# Power.net
KiCad netlist of a schematic drawn in Altium Designer
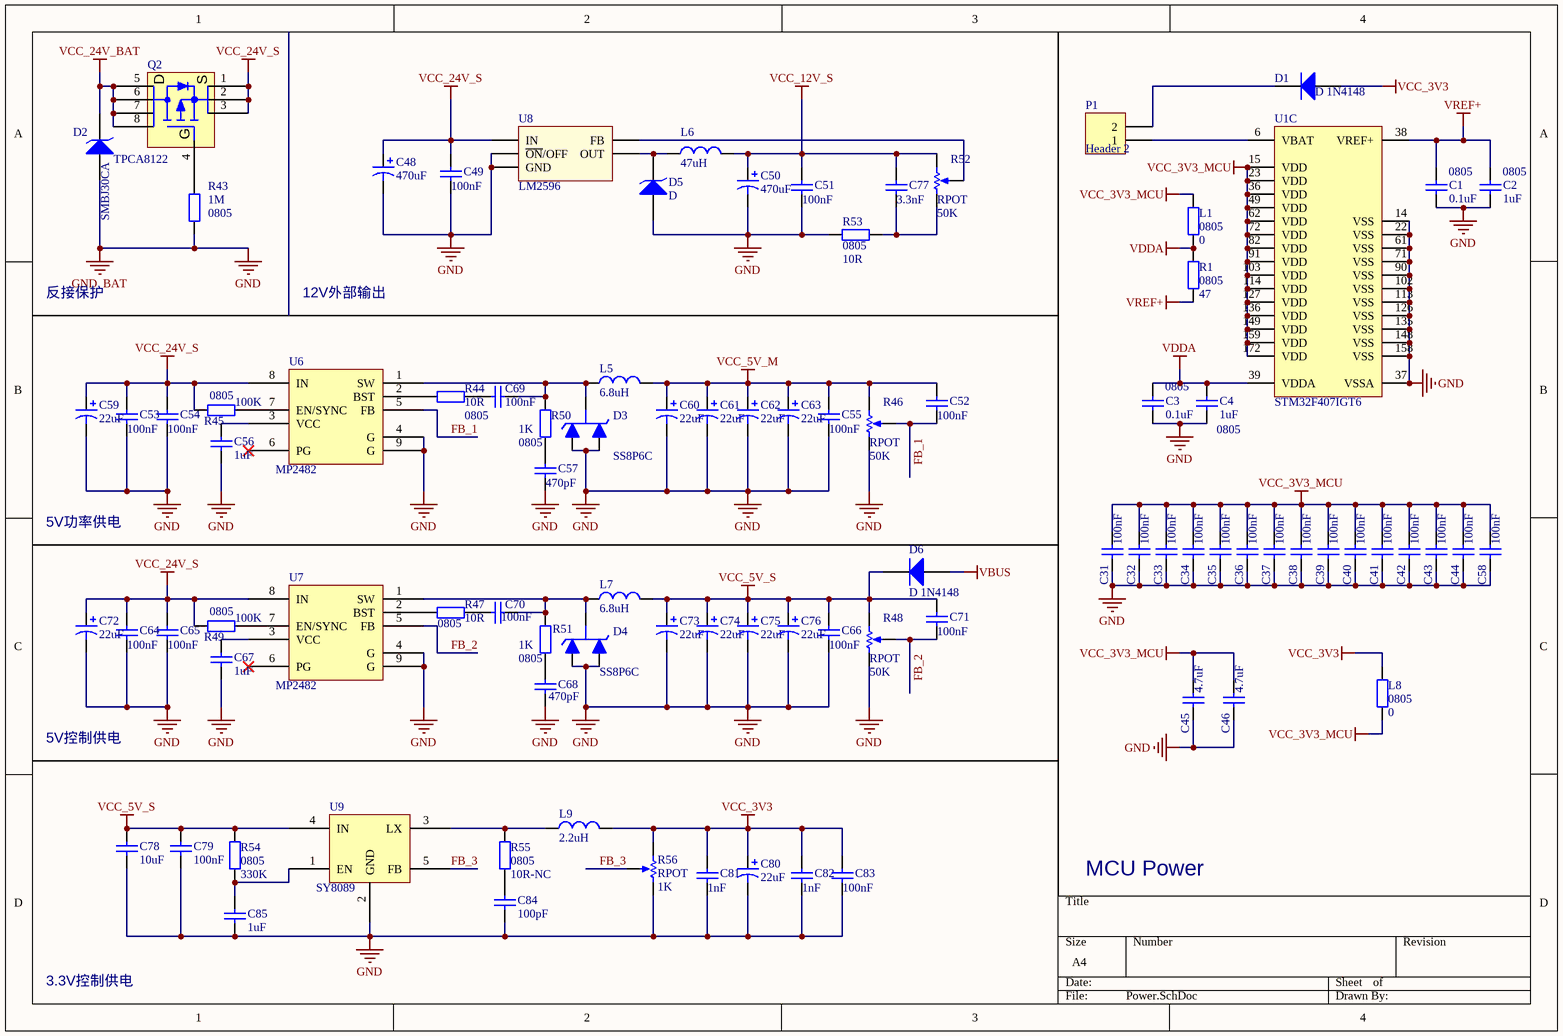
[diagram p0: Power.SchDoc]

(export (version "E")
  (design (tool "Eeschema 10.0.6"))
  (components
    (comp (ref "C1")
      (value "0805")
      (footprint "C 0603_L")
      (fields (field (name "ALTIUM_VALUE") "0.1uF"))
      (libsource (lib "QT") (part "CAP"))
    )
    (comp (ref "C2")
      (value "0805")
      (footprint "C 0603_L")
      (fields (field (name "ALTIUM_VALUE") "1uF"))
      (libsource (lib "QT") (part "CAP"))
    )
    (comp (ref "C3")
      (value "0805")
      (footprint "C 0603_L")
      (fields (field (name "ALTIUM_VALUE") "0.1uF"))
      (libsource (lib "QT") (part "CAP"))
    )
    (comp (ref "C4")
      (value "0805")
      (footprint "C 0603_L")
      (fields (field (name "ALTIUM_VALUE") "1uF"))
      (libsource (lib "QT") (part "CAP"))
    )
    (comp (ref "C31")
      (value "100nF")
      (footprint "C 0603_L")
      (fields (field (name "Comment") "0805"))
      (libsource (lib "QT") (part "CAP"))
    )
    (comp (ref "C32")
      (value "100nF")
      (footprint "C 0603_L")
      (fields (field (name "Comment") "0805"))
      (libsource (lib "QT") (part "CAP"))
    )
    (comp (ref "C33")
      (value "100nF")
      (footprint "C 0603_L")
      (fields (field (name "Comment") "0805"))
      (libsource (lib "QT") (part "CAP"))
    )
    (comp (ref "C34")
      (value "100nF")
      (footprint "C 0603_L")
      (fields (field (name "Comment") "0805"))
      (libsource (lib "QT") (part "CAP"))
    )
    (comp (ref "C35")
      (value "100nF")
      (footprint "C 0603_L")
      (fields (field (name "Comment") "0805"))
      (libsource (lib "QT") (part "CAP"))
    )
    (comp (ref "C36")
      (value "100nF")
      (footprint "C 0603_L")
      (fields (field (name "Comment") "0805"))
      (libsource (lib "QT") (part "CAP"))
    )
    (comp (ref "C37")
      (value "100nF")
      (footprint "C 0603_L")
      (fields (field (name "Comment") "0805"))
      (libsource (lib "QT") (part "CAP"))
    )
    (comp (ref "C38")
      (value "100nF")
      (footprint "C 0603_L")
      (fields (field (name "Comment") "0805"))
      (libsource (lib "QT") (part "CAP"))
    )
    (comp (ref "C39")
      (value "100nF")
      (footprint "C 0603_L")
      (fields (field (name "Comment") "0805"))
      (libsource (lib "QT") (part "CAP"))
    )
    (comp (ref "C40")
      (value "100nF")
      (footprint "C 0603_L")
      (fields (field (name "Comment") "0805"))
      (libsource (lib "QT") (part "CAP"))
    )
    (comp (ref "C41")
      (value "100nF")
      (footprint "C 0603_L")
      (fields (field (name "Comment") "0805"))
      (libsource (lib "QT") (part "CAP"))
    )
    (comp (ref "C42")
      (value "100nF")
      (footprint "C 0603_L")
      (fields (field (name "Comment") "0805"))
      (libsource (lib "QT") (part "CAP"))
    )
    (comp (ref "C43")
      (value "100nF")
      (footprint "C 0603_L")
      (fields (field (name "Comment") "0805"))
      (libsource (lib "QT") (part "CAP"))
    )
    (comp (ref "C44")
      (value "100nF")
      (footprint "C 0603_L")
      (fields (field (name "Comment") "0805"))
      (libsource (lib "QT") (part "CAP"))
    )
    (comp (ref "C45")
      (value "4.7uF")
      (footprint "C 0805_M")
      (fields (field (name "Comment") "0805"))
      (libsource (lib "QT") (part "CAP"))
    )
    (comp (ref "C46")
      (value "4.7uF")
      (footprint "C 0805_M")
      (fields (field (name "Comment") "0805"))
      (libsource (lib "QT") (part "CAP"))
    )
    (comp (ref "C48")
      (value "470uF")
      (footprint "CM E(8*10.2)")
      (fields (field (name "Comment") "CAP-ELEC"))
      (libsource (lib "QT") (part "CAP-ELEC"))
    )
    (comp (ref "C49")
      (value "100nF")
      (footprint "C 0805_L")
      (fields (field (name "Comment") "CAP"))
      (libsource (lib "QT") (part "CAP"))
    )
    (comp (ref "C50")
      (value "470uF")
      (footprint "CM E(8*10.2)")
      (fields (field (name "Comment") "CAP-ELEC"))
      (libsource (lib "QT") (part "CAP-ELEC"))
    )
    (comp (ref "C51")
      (value "100nF")
      (footprint "C 0805_L")
      (fields (field (name "Comment") "CAP"))
      (libsource (lib "QT") (part "CAP"))
    )
    (comp (ref "C52")
      (value "100nF")
      (footprint "C 0805_L")
      (fields (field (name "Comment") "CAP"))
      (libsource (lib "QT") (part "CAP"))
    )
    (comp (ref "C53")
      (value "100nF")
      (footprint "C 0805_L")
      (fields (field (name "Comment") "CAP"))
      (libsource (lib "QT") (part "CAP"))
    )
    (comp (ref "C54")
      (value "100nF")
      (footprint "C 0805_L")
      (fields (field (name "Comment") "CAP"))
      (libsource (lib "QT") (part "CAP"))
    )
    (comp (ref "C55")
      (value "100nF")
      (footprint "C 0805_L")
      (fields (field (name "Comment") "CAP"))
      (libsource (lib "QT") (part "CAP"))
    )
    (comp (ref "C56")
      (value "1uF")
      (footprint "C 0805_L")
      (fields (field (name "Comment") "CAP"))
      (libsource (lib "QT") (part "CAP"))
    )
    (comp (ref "C57")
      (value "470pF")
      (footprint "C 0805_L")
      (fields (field (name "Comment") "CAP"))
      (libsource (lib "QT") (part "CAP"))
    )
    (comp (ref "C58")
      (value "100nF")
      (footprint "C 0603_L")
      (fields (field (name "Comment") "0805"))
      (libsource (lib "QT") (part "CAP"))
    )
    (comp (ref "C59")
      (value "22uF")
      (footprint "CD C(6032)")
      (fields (field (name "Comment") "CAP-ELEC"))
      (libsource (lib "QT") (part "CAP-ELEC"))
    )
    (comp (ref "C60")
      (value "22uF")
      (footprint "CD C(6032)")
      (fields (field (name "Comment") "CAP-ELEC"))
      (libsource (lib "QT") (part "CAP-ELEC"))
    )
    (comp (ref "C61")
      (value "22uF")
      (footprint "CD C(6032)")
      (fields (field (name "Comment") "CAP-ELEC"))
      (libsource (lib "QT") (part "CAP-ELEC"))
    )
    (comp (ref "C62")
      (value "22uF")
      (footprint "CD C(6032)")
      (fields (field (name "Comment") "CAP-ELEC"))
      (libsource (lib "QT") (part "CAP-ELEC"))
    )
    (comp (ref "C63")
      (value "22uF")
      (footprint "CD C(6032)")
      (fields (field (name "Comment") "CAP-ELEC"))
      (libsource (lib "QT") (part "CAP-ELEC"))
    )
    (comp (ref "C64")
      (value "100nF")
      (footprint "C 0805_L")
      (fields (field (name "Comment") "CAP"))
      (libsource (lib "QT") (part "CAP"))
    )
    (comp (ref "C65")
      (value "100nF")
      (footprint "C 0805_L")
      (fields (field (name "Comment") "CAP"))
      (libsource (lib "QT") (part "CAP"))
    )
    (comp (ref "C66")
      (value "100nF")
      (footprint "C 0805_L")
      (fields (field (name "Comment") "CAP"))
      (libsource (lib "QT") (part "CAP"))
    )
    (comp (ref "C67")
      (value "1uF")
      (footprint "C 0805_L")
      (fields (field (name "Comment") "CAP"))
      (libsource (lib "QT") (part "CAP"))
    )
    (comp (ref "C68")
      (value "470pF")
      (footprint "C 0805_L")
      (fields (field (name "Comment") "CAP"))
      (libsource (lib "QT") (part "CAP"))
    )
    (comp (ref "C69")
      (value "100nF")
      (footprint "C 0805_L")
      (fields (field (name "Comment") "CAP"))
      (libsource (lib "QT") (part "CAP"))
    )
    (comp (ref "C70")
      (value "100nF")
      (footprint "C 0805_L")
      (fields (field (name "Comment") "CAP"))
      (libsource (lib "QT") (part "CAP"))
    )
    (comp (ref "C71")
      (value "100nF")
      (footprint "C 0805_L")
      (fields (field (name "Comment") "CAP"))
      (libsource (lib "QT") (part "CAP"))
    )
    (comp (ref "C72")
      (value "22uF")
      (footprint "CD C(6032)")
      (fields (field (name "Comment") "CAP-ELEC"))
      (libsource (lib "QT") (part "CAP-ELEC"))
    )
    (comp (ref "C73")
      (value "22uF")
      (footprint "CD C(6032)")
      (fields (field (name "Comment") "CAP-ELEC"))
      (libsource (lib "QT") (part "CAP-ELEC"))
    )
    (comp (ref "C74")
      (value "22uF")
      (footprint "CD C(6032)")
      (fields (field (name "Comment") "CAP-ELEC"))
      (libsource (lib "QT") (part "CAP-ELEC"))
    )
    (comp (ref "C75")
      (value "22uF")
      (footprint "CD C(6032)")
      (fields (field (name "Comment") "CAP-ELEC"))
      (libsource (lib "QT") (part "CAP-ELEC"))
    )
    (comp (ref "C76")
      (value "22uF")
      (footprint "CD C(6032)")
      (fields (field (name "Comment") "CAP-ELEC"))
      (libsource (lib "QT") (part "CAP-ELEC"))
    )
    (comp (ref "C77")
      (value "3.3nF")
      (footprint "C 0805_L")
      (fields (field (name "Comment") "CAP"))
      (libsource (lib "QT") (part "CAP"))
    )
    (comp (ref "C78")
      (value "10uF")
      (footprint "C 0805_L")
      (fields (field (name "Comment") "CAP"))
      (libsource (lib "QT") (part "CAP"))
    )
    (comp (ref "C79")
      (value "100nF")
      (footprint "C 0805_L")
      (fields (field (name "Comment") "CAP"))
      (libsource (lib "QT") (part "CAP"))
    )
    (comp (ref "C80")
      (value "22uF")
      (footprint "CD C(6032)")
      (fields (field (name "Comment") "CAP-ELEC"))
      (libsource (lib "QT") (part "CAP-ELEC"))
    )
    (comp (ref "C81")
      (value "1nF")
      (footprint "C 0805_L")
      (fields (field (name "Comment") "CAP"))
      (libsource (lib "QT") (part "CAP"))
    )
    (comp (ref "C82")
      (value "1nF")
      (footprint "C 0805_L")
      (fields (field (name "Comment") "CAP"))
      (libsource (lib "QT") (part "CAP"))
    )
    (comp (ref "C83")
      (value "100nF")
      (footprint "C 0805_L")
      (fields (field (name "Comment") "CAP"))
      (libsource (lib "QT") (part "CAP"))
    )
    (comp (ref "C84")
      (value "100pF")
      (footprint "C 0805_L")
      (fields (field (name "Comment") "CAP"))
      (libsource (lib "QT") (part "CAP"))
    )
    (comp (ref "C85")
      (value "1uF")
      (footprint "C 0805_L")
      (fields (field (name "Comment") "CAP"))
      (libsource (lib "QT") (part "CAP"))
    )
    (comp (ref "D1")
      (value "D 1N4148")
      (footprint "SOD-523")
      (description "High Conductance Fast Diode")
      (fields (field (name "PUBLISHER") "Altium Limited"))
      (libsource (lib "QT") (part "D 1N4148"))
    )
    (comp (ref "D2")
      (value "SMBJ30CA")
      (footprint "SMB")
      (description "High Conductance Fast Diode")
      (fields (field (name "PUBLISHER") "Altium Limited"))
      (libsource (lib "QT") (part "D"))
    )
    (comp (ref "D3") (value "SS8P6C") (footprint "TO-277") (libsource (lib "常用元件库") (part "SS8P6C")))
    (comp (ref "D4") (value "SS8P6C") (footprint "TO-277") (libsource (lib "常用元件库") (part "SS8P6C")))
    (comp (ref "D5")
      (value "D")
      (footprint "SOD-123")
      (description "High Conductance Fast Diode")
      (fields (field (name "PUBLISHER") "Altium Limited"))
      (libsource (lib "QT") (part "D"))
    )
    (comp (ref "D6")
      (value "D 1N4148")
      (footprint "SOD-123")
      (description "High Conductance Fast Diode")
      (fields (field (name "PUBLISHER") "Altium Limited"))
      (libsource (lib "QT") (part "D 1N4148"))
    )
    (comp (ref "L1")
      (value "0805")
      (footprint "R 0402_L")
      (description "Resistor")
      (fields (field (name "ALTIUM_VALUE") "0") (field (name "PUBLISHER") "Altium Limited"))
      (libsource (lib "QT") (part "RES2"))
    )
    (comp (ref "L5")
      (value "6.8uH")
      (footprint "L-SMD-10")
      (description "电感")
      (fields (field (name "Comment") "Inductor") (field (name "PUBLISHER") "Altium Limited"))
      (libsource (lib "Fszhang") (part "Inductor"))
    )
    (comp (ref "L6")
      (value "47uH")
      (footprint "L-SMD-12")
      (description "电感")
      (fields (field (name "Comment") "Inductor") (field (name "PUBLISHER") "Altium Limited"))
      (libsource (lib "Fszhang") (part "Inductor"))
    )
    (comp (ref "L7")
      (value "6.8uH")
      (footprint "L-SMD-10")
      (description "电感")
      (fields (field (name "Comment") "Inductor") (field (name "PUBLISHER") "Altium Limited"))
      (libsource (lib "Fszhang") (part "Inductor"))
    )
    (comp (ref "L8")
      (value "0805")
      (footprint "R 0402_L")
      (description "Resistor")
      (fields (field (name "ALTIUM_VALUE") "0") (field (name "PUBLISHER") "Altium Limited"))
      (libsource (lib "QT") (part "RES2"))
    )
    (comp (ref "L9")
      (value "2.2uH")
      (footprint "CD52")
      (description "电感")
      (fields (field (name "Comment") "Inductor") (field (name "PUBLISHER") "Altium Limited"))
      (libsource (lib "Fszhang") (part "Inductor"))
    )
    (comp (ref "P1")
      (value "Header 2")
      (footprint "HDR2.54-LI-2P")
      (description "Header, 2-Pin")
      (fields (field (name "PUBLISHER") "Altium Limited"))
      (libsource (lib "QT") (part "Header 2"))
    )
    (comp (ref "Q2") (value "TPCA8122") (footprint "PSOP8") (libsource (lib "常用元件库") (part "TPCA8122")))
    (comp (ref "R1")
      (value "0805")
      (footprint "R 0402_L")
      (description "Resistor")
      (fields (field (name "ALTIUM_VALUE") "47") (field (name "PUBLISHER") "Altium Limited"))
      (libsource (lib "QT") (part "RES2"))
    )
    (comp (ref "R43")
      (value "0805")
      (footprint "R 0805_L")
      (description "Resistor")
      (fields (field (name "ALTIUM_VALUE") "1M") (field (name "PUBLISHER") "Altium Limited"))
      (libsource (lib "QT") (part "RES2"))
    )
    (comp (ref "R44")
      (value "0805")
      (footprint "R 0805_L")
      (description "Resistor")
      (fields (field (name "ALTIUM_VALUE") "10R") (field (name "PUBLISHER") "Altium Limited"))
      (libsource (lib "") (part "RES2_2"))
    )
    (comp (ref "R45")
      (value "0805")
      (footprint "R 0805_L")
      (description "Resistor")
      (fields (field (name "ALTIUM_VALUE") "100K") (field (name "PUBLISHER") "Altium Limited"))
      (libsource (lib "") (part "RES2_2"))
    )
    (comp (ref "R46")
      (value "RPOT")
      (footprint "3296W")
      (description "Potentiometer")
      (fields (field (name "ALTIUM_VALUE") "50K") (field (name "PUBLISHER") "Altium Limited"))
      (libsource (lib "QT") (part "RPOT"))
    )
    (comp (ref "R47")
      (value "0805")
      (footprint "R 0805_L")
      (description "Resistor")
      (fields (field (name "ALTIUM_VALUE") "10R") (field (name "PUBLISHER") "Altium Limited"))
      (libsource (lib "") (part "RES2_2"))
    )
    (comp (ref "R48")
      (value "RPOT")
      (footprint "3296W")
      (description "Potentiometer")
      (fields (field (name "ALTIUM_VALUE") "50K") (field (name "PUBLISHER") "Altium Limited"))
      (libsource (lib "QT") (part "RPOT"))
    )
    (comp (ref "R49")
      (value "0805")
      (footprint "R 0805_L")
      (description "Resistor")
      (fields (field (name "ALTIUM_VALUE") "100K") (field (name "PUBLISHER") "Altium Limited"))
      (libsource (lib "") (part "RES2_2"))
    )
    (comp (ref "R50")
      (value "0805")
      (footprint "R 0805_L")
      (description "Resistor")
      (fields (field (name "ALTIUM_VALUE") "1K") (field (name "PUBLISHER") "Altium Limited"))
      (libsource (lib "QT") (part "RES2"))
    )
    (comp (ref "R51")
      (value "0805")
      (footprint "R 0805_L")
      (description "Resistor")
      (fields (field (name "ALTIUM_VALUE") "1K") (field (name "PUBLISHER") "Altium Limited"))
      (libsource (lib "QT") (part "RES2"))
    )
    (comp (ref "R52")
      (value "RPOT")
      (footprint "3296W")
      (description "Potentiometer")
      (fields (field (name "ALTIUM_VALUE") "50K") (field (name "PUBLISHER") "Altium Limited"))
      (libsource (lib "QT") (part "RPOT"))
    )
    (comp (ref "R53")
      (value "0805")
      (footprint "R 0805_L")
      (description "Resistor")
      (fields (field (name "ALTIUM_VALUE") "10R") (field (name "PUBLISHER") "Altium Limited"))
      (libsource (lib "") (part "RES2_1"))
    )
    (comp (ref "R54")
      (value "0805")
      (footprint "R 0805_L")
      (description "Resistor")
      (fields (field (name "ALTIUM_VALUE") "330K") (field (name "PUBLISHER") "Altium Limited"))
      (libsource (lib "QT") (part "RES2"))
    )
    (comp (ref "R55")
      (value "0805")
      (footprint "R 0805_L")
      (description "Resistor")
      (fields (field (name "ALTIUM_VALUE") "10R-NC") (field (name "PUBLISHER") "Altium Limited"))
      (libsource (lib "QT") (part "RES2"))
    )
    (comp (ref "R56")
      (value "RPOT")
      (footprint "3296W")
      (description "Potentiometer")
      (fields (field (name "ALTIUM_VALUE") "1K") (field (name "PUBLISHER") "Altium Limited"))
      (libsource (lib "QT") (part "RPOT"))
    )
    (comp (ref "U1")
      (value "STM32F407IGT6")
      (footprint "STM-LQFP176_N")
      (fields (field (name "MANUFACTURER") "STMicroelectronics"))
      (libsource (lib "STMicroelectronics STM32 F4") (part "STM32F407IGT6"))
    )
    (comp (ref "U6") (value "MP2482") (footprint "SOIC9N") (libsource (lib "常用元件库") (part "MP2482")))
    (comp (ref "U7") (value "MP2482") (footprint "SOIC9N") (libsource (lib "常用元件库") (part "MP2482")))
    (comp (ref "U8") (value "LM2596") (footprint "TO263-5A") (libsource (lib "QT") (part "LM2576S")))
    (comp (ref "U9") (value "SY8089") (footprint "SOT-23-5L") (libsource (lib "常用元件库") (part "SY8089")))
  )
  (nets
    (net (code "1") (name "/FB_1") (class "Default")
      (node (ref "C52") (pin "2") (pinfunction "2_2") (pintype "passive"))
      (node (ref "R46") (pin "2") (pintype "passive"))
      (node (ref "U6") (pin "5") (pinfunction "FB_5") (pintype "passive"))
    )
    (net (code "2") (name "/FB_2") (class "Default")
      (node (ref "C71") (pin "2") (pinfunction "2_2") (pintype "passive"))
      (node (ref "R48") (pin "2") (pintype "passive"))
      (node (ref "U7") (pin "5") (pinfunction "FB_5") (pintype "passive"))
    )
    (net (code "3") (name "/FB_3") (class "Default")
      (node (ref "R56") (pin "2") (pintype "passive"))
      (node (ref "U9") (pin "5") (pinfunction "FB_5") (pintype "passive"))
    )
    (net (code "4") (name "GND") (class "Default")
      (node (ref "C1") (pin "1") (pinfunction "1_1") (pintype "passive"))
      (node (ref "C2") (pin "1") (pinfunction "1_1") (pintype "passive"))
      (node (ref "C3") (pin "1") (pinfunction "1_1") (pintype "passive"))
      (node (ref "C31") (pin "1") (pinfunction "1_1") (pintype "passive"))
      (node (ref "C32") (pin "1") (pinfunction "1_1") (pintype "passive"))
      (node (ref "C33") (pin "1") (pinfunction "1_1") (pintype "passive"))
      (node (ref "C34") (pin "1") (pinfunction "1_1") (pintype "passive"))
      (node (ref "C35") (pin "1") (pinfunction "1_1") (pintype "passive"))
      (node (ref "C36") (pin "1") (pinfunction "1_1") (pintype "passive"))
      (node (ref "C37") (pin "1") (pinfunction "1_1") (pintype "passive"))
      (node (ref "C38") (pin "1") (pinfunction "1_1") (pintype "passive"))
      (node (ref "C39") (pin "1") (pinfunction "1_1") (pintype "passive"))
      (node (ref "C4") (pin "1") (pinfunction "1_1") (pintype "passive"))
      (node (ref "C40") (pin "1") (pinfunction "1_1") (pintype "passive"))
      (node (ref "C41") (pin "1") (pinfunction "1_1") (pintype "passive"))
      (node (ref "C42") (pin "1") (pinfunction "1_1") (pintype "passive"))
      (node (ref "C43") (pin "1") (pinfunction "1_1") (pintype "passive"))
      (node (ref "C44") (pin "1") (pinfunction "1_1") (pintype "passive"))
      (node (ref "C45") (pin "1") (pinfunction "1_1") (pintype "passive"))
      (node (ref "C46") (pin "1") (pinfunction "1_1") (pintype "passive"))
      (node (ref "C48") (pin "2") (pinfunction "2_2") (pintype "passive"))
      (node (ref "C49") (pin "2") (pinfunction "2_2") (pintype "passive"))
      (node (ref "C50") (pin "2") (pinfunction "2_2") (pintype "passive"))
      (node (ref "C51") (pin "2") (pinfunction "2_2") (pintype "passive"))
      (node (ref "C53") (pin "2") (pinfunction "2_2") (pintype "passive"))
      (node (ref "C54") (pin "2") (pinfunction "2_2") (pintype "passive"))
      (node (ref "C55") (pin "2") (pinfunction "2_2") (pintype "passive"))
      (node (ref "C56") (pin "1") (pinfunction "1_1") (pintype "passive"))
      (node (ref "C57") (pin "1") (pinfunction "1_1") (pintype "passive"))
      (node (ref "C58") (pin "1") (pinfunction "1_1") (pintype "passive"))
      (node (ref "C59") (pin "2") (pinfunction "2_2") (pintype "passive"))
      (node (ref "C60") (pin "2") (pinfunction "2_2") (pintype "passive"))
      (node (ref "C61") (pin "2") (pinfunction "2_2") (pintype "passive"))
      (node (ref "C62") (pin "2") (pinfunction "2_2") (pintype "passive"))
      (node (ref "C63") (pin "2") (pinfunction "2_2") (pintype "passive"))
      (node (ref "C64") (pin "2") (pinfunction "2_2") (pintype "passive"))
      (node (ref "C65") (pin "2") (pinfunction "2_2") (pintype "passive"))
      (node (ref "C66") (pin "2") (pinfunction "2_2") (pintype "passive"))
      (node (ref "C67") (pin "1") (pinfunction "1_1") (pintype "passive"))
      (node (ref "C68") (pin "1") (pinfunction "1_1") (pintype "passive"))
      (node (ref "C72") (pin "2") (pinfunction "2_2") (pintype "passive"))
      (node (ref "C73") (pin "2") (pinfunction "2_2") (pintype "passive"))
      (node (ref "C74") (pin "2") (pinfunction "2_2") (pintype "passive"))
      (node (ref "C75") (pin "2") (pinfunction "2_2") (pintype "passive"))
      (node (ref "C76") (pin "2") (pinfunction "2_2") (pintype "passive"))
      (node (ref "C78") (pin "1") (pinfunction "1_1") (pintype "passive"))
      (node (ref "C79") (pin "1") (pinfunction "1_1") (pintype "passive"))
      (node (ref "C80") (pin "2") (pinfunction "2_2") (pintype "passive"))
      (node (ref "C81") (pin "2") (pinfunction "2_2") (pintype "passive"))
      (node (ref "C82") (pin "2") (pinfunction "2_2") (pintype "passive"))
      (node (ref "C83") (pin "2") (pinfunction "2_2") (pintype "passive"))
      (node (ref "C84") (pin "1") (pinfunction "1_1") (pintype "passive"))
      (node (ref "C85") (pin "1") (pinfunction "1_1") (pintype "passive"))
      (node (ref "D2") (pin "1") (pinfunction "A_1") (pintype "passive"))
      (node (ref "D3") (pin "1") (pintype "passive"))
      (node (ref "D3") (pin "2") (pintype "passive"))
      (node (ref "D4") (pin "1") (pintype "passive"))
      (node (ref "D4") (pin "2") (pintype "passive"))
      (node (ref "D5") (pin "1") (pinfunction "A_1") (pintype "passive"))
      (node (ref "R43") (pin "1") (pinfunction "1_1") (pintype "passive"))
      (node (ref "R46") (pin "1") (pintype "passive"))
      (node (ref "R48") (pin "1") (pintype "passive"))
      (node (ref "R53") (pin "2") (pinfunction "2_2") (pintype "passive"))
      (node (ref "R56") (pin "3") (pintype "passive"))
      (node (ref "U1") (pin "102") (pinfunction "VSS_102") (pintype "power_in"))
      (node (ref "U1") (pin "113") (pinfunction "VSS_113") (pintype "power_in"))
      (node (ref "U1") (pin "126") (pinfunction "VSS_126") (pintype "power_in"))
      (node (ref "U1") (pin "135") (pinfunction "VSS_135") (pintype "power_in"))
      (node (ref "U1") (pin "14") (pinfunction "VSS_14") (pintype "power_in"))
      (node (ref "U1") (pin "148") (pinfunction "VSS_148") (pintype "power_in"))
      (node (ref "U1") (pin "158") (pinfunction "VSS_158") (pintype "power_in"))
      (node (ref "U1") (pin "22") (pinfunction "VSS_22") (pintype "power_in"))
      (node (ref "U1") (pin "37") (pinfunction "VSSA_37") (pintype "power_in"))
      (node (ref "U1") (pin "61") (pinfunction "VSS_61") (pintype "power_in"))
      (node (ref "U1") (pin "71") (pinfunction "VSS_71") (pintype "power_in"))
      (node (ref "U1") (pin "90") (pinfunction "VSS_90") (pintype "power_in"))
      (node (ref "U6") (pin "4") (pinfunction "G_4") (pintype "passive"))
      (node (ref "U6") (pin "9") (pinfunction "G_9") (pintype "passive"))
      (node (ref "U7") (pin "4") (pinfunction "G_4") (pintype "passive"))
      (node (ref "U7") (pin "9") (pinfunction "G_9") (pintype "passive"))
      (node (ref "U8") (pin "3") (pinfunction "GND_3") (pintype "passive"))
      (node (ref "U8") (pin "5") (pinfunction "~{ON}/OFF_5") (pintype "passive"))
      (node (ref "U9") (pin "2") (pinfunction "GND_2") (pintype "passive"))
    )
    (net (code "5") (name "Net-(C57-Pad2)") (class "Default")
      (node (ref "C57") (pin "2") (pinfunction "2_2") (pintype "passive"))
      (node (ref "R50") (pin "1") (pinfunction "1_1") (pintype "passive"))
    )
    (net (code "6") (name "Net-(C68-Pad2)") (class "Default")
      (node (ref "C68") (pin "2") (pinfunction "2_2") (pintype "passive"))
      (node (ref "R51") (pin "1") (pinfunction "1_1") (pintype "passive"))
    )
    (net (code "7") (name "Net-(C69-Pad2)") (class "Default")
      (node (ref "C69") (pin "2") (pinfunction "2_2") (pintype "passive"))
      (node (ref "R44") (pin "2") (pinfunction "2_2") (pintype "passive"))
    )
    (net (code "8") (name "Net-(C70-Pad2)") (class "Default")
      (node (ref "C70") (pin "2") (pinfunction "2_2") (pintype "passive"))
      (node (ref "R47") (pin "2") (pinfunction "2_2") (pintype "passive"))
    )
    (net (code "9") (name "Net-(C77-Pad2)") (class "Default")
      (node (ref "C77") (pin "2") (pinfunction "2_2") (pintype "passive"))
      (node (ref "R52") (pin "1") (pintype "passive"))
      (node (ref "R53") (pin "1") (pinfunction "1_1") (pintype "passive"))
    )
    (net (code "10") (name "Net-(C84-Pad2)") (class "Default")
      (node (ref "C84") (pin "2") (pinfunction "2_2") (pintype "passive"))
      (node (ref "R55") (pin "1") (pinfunction "1_1") (pintype "passive"))
    )
    (net (code "11") (name "Net-(D1-K)") (class "Default")
      (node (ref "D1") (pin "2") (pinfunction "K_2") (pintype "passive"))
      (node (ref "P1") (pin "2") (pinfunction "2_2") (pintype "passive"))
    )
    (net (code "12") (name "Net-(D5-K)") (class "Default")
      (node (ref "D5") (pin "2") (pinfunction "K_2") (pintype "passive"))
      (node (ref "L6") (pin "1") (pinfunction "1_1") (pintype "passive"))
      (node (ref "U8") (pin "2") (pinfunction "OUT_2") (pintype "passive"))
    )
    (net (code "13") (name "Net-(Q2-G)") (class "Default")
      (node (ref "Q2") (pin "4") (pinfunction "G_4") (pintype "passive"))
      (node (ref "R43") (pin "2") (pinfunction "2_2") (pintype "passive"))
    )
    (net (code "14") (name "Net-(U1C-VBAT)") (class "Default")
      (node (ref "P1") (pin "1") (pinfunction "1_1") (pintype "passive"))
      (node (ref "U1") (pin "6") (pinfunction "VBAT_6") (pintype "power_in"))
    )
    (net (code "15") (name "Net-(U6-BST)") (class "Default")
      (node (ref "R44") (pin "1") (pinfunction "1_1") (pintype "passive"))
      (node (ref "U6") (pin "2") (pinfunction "BST_2") (pintype "passive"))
    )
    (net (code "16") (name "Net-(U6-EN{slash}SYNC)") (class "Default")
      (node (ref "R45") (pin "2") (pinfunction "2_2") (pintype "passive"))
      (node (ref "U6") (pin "7") (pinfunction "EN/SYNC_7") (pintype "passive"))
    )
    (net (code "17") (name "Net-(U6-SW)") (class "Default")
      (node (ref "C69") (pin "1") (pinfunction "1_1") (pintype "passive"))
      (node (ref "D3") (pin "3") (pintype "passive"))
      (node (ref "L5") (pin "1") (pinfunction "1_1") (pintype "passive"))
      (node (ref "R50") (pin "2") (pinfunction "2_2") (pintype "passive"))
      (node (ref "U6") (pin "1") (pinfunction "SW_1") (pintype "passive"))
    )
    (net (code "18") (name "Net-(U6-VCC)") (class "Default")
      (node (ref "C56") (pin "2") (pinfunction "2_2") (pintype "passive"))
      (node (ref "U6") (pin "3") (pinfunction "VCC_3") (pintype "passive"))
    )
    (net (code "19") (name "Net-(U7-BST)") (class "Default")
      (node (ref "R47") (pin "1") (pinfunction "1_1") (pintype "passive"))
      (node (ref "U7") (pin "2") (pinfunction "BST_2") (pintype "passive"))
    )
    (net (code "20") (name "Net-(U7-EN{slash}SYNC)") (class "Default")
      (node (ref "R49") (pin "2") (pinfunction "2_2") (pintype "passive"))
      (node (ref "U7") (pin "7") (pinfunction "EN/SYNC_7") (pintype "passive"))
    )
    (net (code "21") (name "Net-(U7-SW)") (class "Default")
      (node (ref "C70") (pin "1") (pinfunction "1_1") (pintype "passive"))
      (node (ref "D4") (pin "3") (pintype "passive"))
      (node (ref "L7") (pin "1") (pinfunction "1_1") (pintype "passive"))
      (node (ref "R51") (pin "2") (pinfunction "2_2") (pintype "passive"))
      (node (ref "U7") (pin "1") (pinfunction "SW_1") (pintype "passive"))
    )
    (net (code "22") (name "Net-(U7-VCC)") (class "Default")
      (node (ref "C67") (pin "2") (pinfunction "2_2") (pintype "passive"))
      (node (ref "U7") (pin "3") (pinfunction "VCC_3") (pintype "passive"))
    )
    (net (code "23") (name "Net-(U8-FB)") (class "Default")
      (node (ref "R52") (pin "2") (pintype "passive"))
      (node (ref "U8") (pin "4") (pinfunction "FB_4") (pintype "passive"))
    )
    (net (code "24") (name "Net-(U9-EN)") (class "Default")
      (node (ref "C85") (pin "2") (pinfunction "2_2") (pintype "passive"))
      (node (ref "R54") (pin "1") (pinfunction "1_1") (pintype "passive"))
      (node (ref "U9") (pin "1") (pinfunction "EN_1") (pintype "passive"))
    )
    (net (code "25") (name "Net-(U9-LX)") (class "Default")
      (node (ref "L9") (pin "1") (pinfunction "1_1") (pintype "passive"))
      (node (ref "R55") (pin "2") (pinfunction "2_2") (pintype "passive"))
      (node (ref "U9") (pin "3") (pinfunction "LX_3") (pintype "passive"))
    )
    (net (code "26") (name "VBUS") (class "Default")
      (node (ref "D6") (pin "1") (pinfunction "A_1") (pintype "passive"))
    )
    (net (code "27") (name "VCC_3V3") (class "Default")
      (node (ref "C80") (pin "1") (pinfunction "1_1") (pintype "passive"))
      (node (ref "C81") (pin "1") (pinfunction "1_1") (pintype "passive"))
      (node (ref "C82") (pin "1") (pinfunction "1_1") (pintype "passive"))
      (node (ref "C83") (pin "1") (pinfunction "1_1") (pintype "passive"))
      (node (ref "D1") (pin "1") (pinfunction "A_1") (pintype "passive"))
      (node (ref "L8") (pin "2") (pinfunction "2_2") (pintype "passive"))
      (node (ref "L9") (pin "2") (pinfunction "2_2") (pintype "passive"))
      (node (ref "R56") (pin "1") (pintype "passive"))
    )
    (net (code "28") (name "VCC_3V3_MCU") (class "Default")
      (node (ref "C31") (pin "2") (pinfunction "2_2") (pintype "passive"))
      (node (ref "C32") (pin "2") (pinfunction "2_2") (pintype "passive"))
      (node (ref "C33") (pin "2") (pinfunction "2_2") (pintype "passive"))
      (node (ref "C34") (pin "2") (pinfunction "2_2") (pintype "passive"))
      (node (ref "C35") (pin "2") (pinfunction "2_2") (pintype "passive"))
      (node (ref "C36") (pin "2") (pinfunction "2_2") (pintype "passive"))
      (node (ref "C37") (pin "2") (pinfunction "2_2") (pintype "passive"))
      (node (ref "C38") (pin "2") (pinfunction "2_2") (pintype "passive"))
      (node (ref "C39") (pin "2") (pinfunction "2_2") (pintype "passive"))
      (node (ref "C40") (pin "2") (pinfunction "2_2") (pintype "passive"))
      (node (ref "C41") (pin "2") (pinfunction "2_2") (pintype "passive"))
      (node (ref "C42") (pin "2") (pinfunction "2_2") (pintype "passive"))
      (node (ref "C43") (pin "2") (pinfunction "2_2") (pintype "passive"))
      (node (ref "C44") (pin "2") (pinfunction "2_2") (pintype "passive"))
      (node (ref "C45") (pin "2") (pinfunction "2_2") (pintype "passive"))
      (node (ref "C46") (pin "2") (pinfunction "2_2") (pintype "passive"))
      (node (ref "C58") (pin "2") (pinfunction "2_2") (pintype "passive"))
      (node (ref "L1") (pin "2") (pinfunction "2_2") (pintype "passive"))
      (node (ref "L8") (pin "1") (pinfunction "1_1") (pintype "passive"))
      (node (ref "U1") (pin "103") (pinfunction "VDD_103") (pintype "power_in"))
      (node (ref "U1") (pin "114") (pinfunction "VDD_114") (pintype "power_in"))
      (node (ref "U1") (pin "127") (pinfunction "VDD_127") (pintype "power_in"))
      (node (ref "U1") (pin "136") (pinfunction "VDD_136") (pintype "power_in"))
      (node (ref "U1") (pin "149") (pinfunction "VDD_149") (pintype "power_in"))
      (node (ref "U1") (pin "15") (pinfunction "VDD_15") (pintype "power_in"))
      (node (ref "U1") (pin "159") (pinfunction "VDD_159") (pintype "power_in"))
      (node (ref "U1") (pin "172") (pinfunction "VDD_172") (pintype "power_in"))
      (node (ref "U1") (pin "23") (pinfunction "VDD_23") (pintype "power_in"))
      (node (ref "U1") (pin "36") (pinfunction "VDD_36") (pintype "power_in"))
      (node (ref "U1") (pin "49") (pinfunction "VDD_49") (pintype "power_in"))
      (node (ref "U1") (pin "62") (pinfunction "VDD_62") (pintype "power_in"))
      (node (ref "U1") (pin "72") (pinfunction "VDD_72") (pintype "power_in"))
      (node (ref "U1") (pin "82") (pinfunction "VDD_82") (pintype "power_in"))
      (node (ref "U1") (pin "91") (pinfunction "VDD_91") (pintype "power_in"))
    )
    (net (code "29") (name "VCC_5V_M") (class "Default")
      (node (ref "C52") (pin "1") (pinfunction "1_1") (pintype "passive"))
      (node (ref "C55") (pin "1") (pinfunction "1_1") (pintype "passive"))
      (node (ref "C60") (pin "1") (pinfunction "1_1") (pintype "passive"))
      (node (ref "C61") (pin "1") (pinfunction "1_1") (pintype "passive"))
      (node (ref "C62") (pin "1") (pinfunction "1_1") (pintype "passive"))
      (node (ref "C63") (pin "1") (pinfunction "1_1") (pintype "passive"))
      (node (ref "L5") (pin "2") (pinfunction "2_2") (pintype "passive"))
      (node (ref "R46") (pin "3") (pintype "passive"))
    )
    (net (code "30") (name "VCC_5V_S") (class "Default")
      (node (ref "C66") (pin "1") (pinfunction "1_1") (pintype "passive"))
      (node (ref "C71") (pin "1") (pinfunction "1_1") (pintype "passive"))
      (node (ref "C73") (pin "1") (pinfunction "1_1") (pintype "passive"))
      (node (ref "C74") (pin "1") (pinfunction "1_1") (pintype "passive"))
      (node (ref "C75") (pin "1") (pinfunction "1_1") (pintype "passive"))
      (node (ref "C76") (pin "1") (pinfunction "1_1") (pintype "passive"))
      (node (ref "C78") (pin "2") (pinfunction "2_2") (pintype "passive"))
      (node (ref "C79") (pin "2") (pinfunction "2_2") (pintype "passive"))
      (node (ref "D6") (pin "2") (pinfunction "K_2") (pintype "passive"))
      (node (ref "L7") (pin "2") (pinfunction "2_2") (pintype "passive"))
      (node (ref "R48") (pin "3") (pintype "passive"))
      (node (ref "R54") (pin "2") (pinfunction "2_2") (pintype "passive"))
      (node (ref "U9") (pin "4") (pinfunction "IN_4") (pintype "passive"))
    )
    (net (code "31") (name "VCC_12V_S") (class "Default")
      (node (ref "C50") (pin "1") (pinfunction "1_1") (pintype "passive"))
      (node (ref "C51") (pin "1") (pinfunction "1_1") (pintype "passive"))
      (node (ref "C77") (pin "1") (pinfunction "1_1") (pintype "passive"))
      (node (ref "L6") (pin "2") (pinfunction "2_2") (pintype "passive"))
      (node (ref "R52") (pin "3") (pintype "passive"))
    )
    (net (code "32") (name "VCC_24V_BAT") (class "Default")
      (node (ref "D2") (pin "2") (pinfunction "K_2") (pintype "passive"))
      (node (ref "Q2") (pin "5") (pinfunction "5_5") (pintype "passive"))
      (node (ref "Q2") (pin "6") (pinfunction "6_6") (pintype "passive"))
      (node (ref "Q2") (pin "7") (pinfunction "7_7") (pintype "passive"))
      (node (ref "Q2") (pin "8") (pinfunction "8_8") (pintype "passive"))
    )
    (net (code "33") (name "VCC_24V_S") (class "Default")
      (node (ref "C48") (pin "1") (pinfunction "1_1") (pintype "passive"))
      (node (ref "C49") (pin "1") (pinfunction "1_1") (pintype "passive"))
      (node (ref "C53") (pin "1") (pinfunction "1_1") (pintype "passive"))
      (node (ref "C54") (pin "1") (pinfunction "1_1") (pintype "passive"))
      (node (ref "C59") (pin "1") (pinfunction "1_1") (pintype "passive"))
      (node (ref "C64") (pin "1") (pinfunction "1_1") (pintype "passive"))
      (node (ref "C65") (pin "1") (pinfunction "1_1") (pintype "passive"))
      (node (ref "C72") (pin "1") (pinfunction "1_1") (pintype "passive"))
      (node (ref "Q2") (pin "1") (pinfunction "S_1") (pintype "passive"))
      (node (ref "Q2") (pin "2") (pinfunction "S_2") (pintype "passive"))
      (node (ref "Q2") (pin "3") (pinfunction "S_3") (pintype "passive"))
      (node (ref "R45") (pin "1") (pinfunction "1_1") (pintype "passive"))
      (node (ref "R49") (pin "1") (pinfunction "1_1") (pintype "passive"))
      (node (ref "U6") (pin "8") (pinfunction "IN_8") (pintype "passive"))
      (node (ref "U7") (pin "8") (pinfunction "IN_8") (pintype "passive"))
      (node (ref "U8") (pin "1") (pinfunction "IN_1") (pintype "passive"))
    )
    (net (code "34") (name "VDDA") (class "Default")
      (node (ref "C3") (pin "2") (pinfunction "2_2") (pintype "passive"))
      (node (ref "C4") (pin "2") (pinfunction "2_2") (pintype "passive"))
      (node (ref "L1") (pin "1") (pinfunction "1_1") (pintype "passive"))
      (node (ref "R1") (pin "2") (pinfunction "2_2") (pintype "passive"))
      (node (ref "U1") (pin "39") (pinfunction "VDDA_39") (pintype "power_in"))
    )
    (net (code "35") (name "VREF+") (class "Default")
      (node (ref "C1") (pin "2") (pinfunction "2_2") (pintype "passive"))
      (node (ref "C2") (pin "2") (pinfunction "2_2") (pintype "passive"))
      (node (ref "R1") (pin "1") (pinfunction "1_1") (pintype "passive"))
      (node (ref "U1") (pin "38") (pinfunction "VREF+_38") (pintype "power_in"))
    )
    (net (code "36") (name "unconnected-(U6-PG-Pad6)") (class "Default")
      (node (ref "U6") (pin "6") (pinfunction "PG_6") (pintype "passive+no_connect"))
    )
    (net (code "37") (name "unconnected-(U7-PG-Pad6)") (class "Default")
      (node (ref "U7") (pin "6") (pinfunction "PG_6") (pintype "passive+no_connect"))
    )
  )
)
